# exterior_enclosure.net
KiCad netlist of a schematic drawn in EAGLE
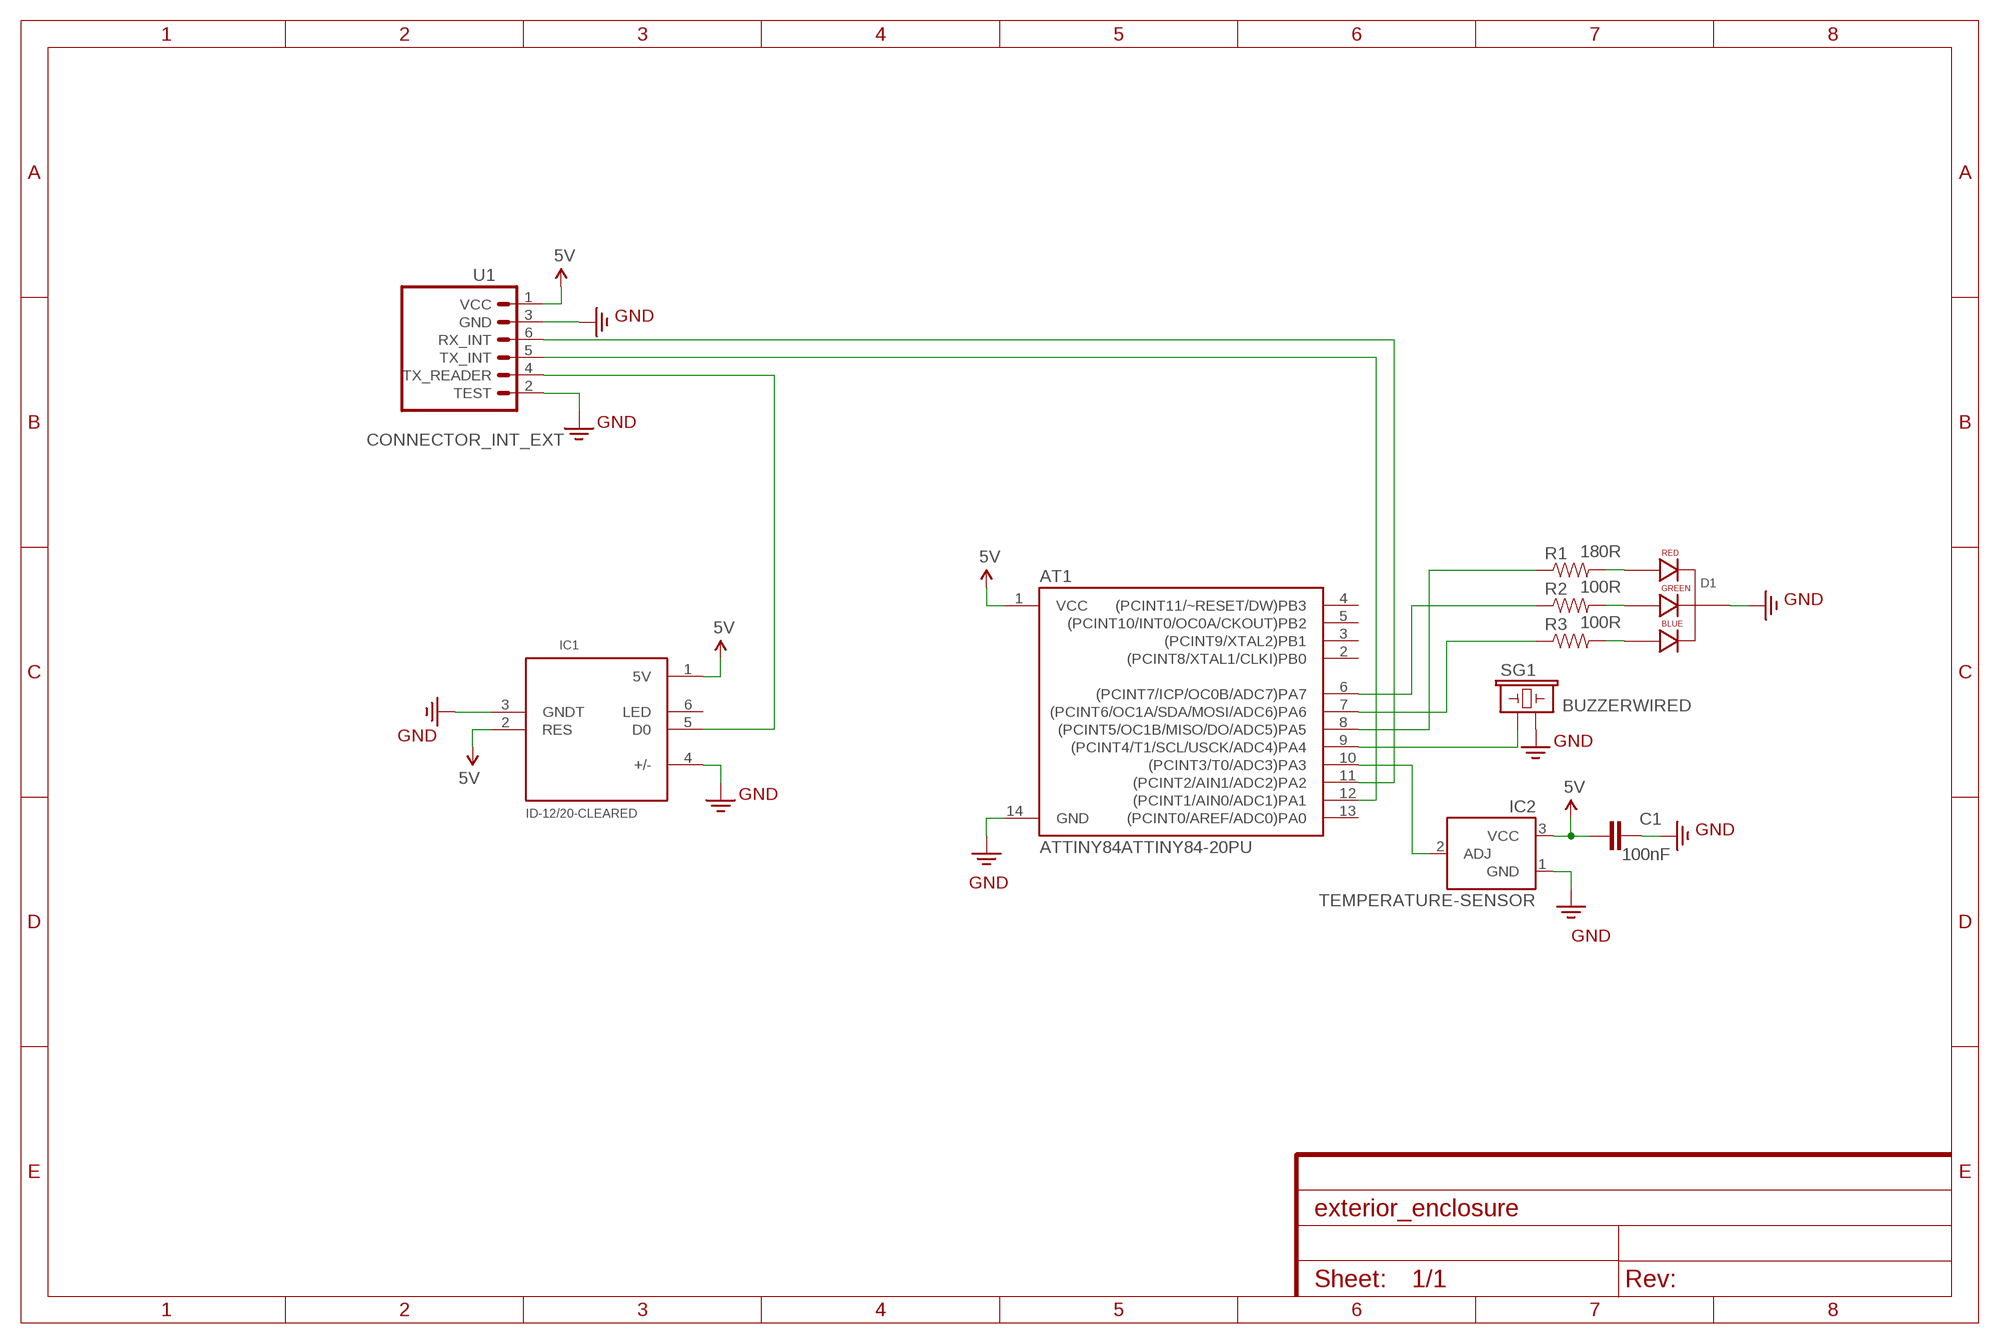
[diagram p0: schematic, sheet 1]

(export (version "E")
  (design (tool "Eeschema 10.0.6"))
  (components
    (comp (ref "AT1")
      (value "ATTINY84ATTINY84-20PU")
      (footprint "eagle-import:DIL14")
      (libsource (lib "eagle-import") (part "ATTINY84ATTINY84-20PU"))
    )
    (comp (ref "C1")
      (value "100nF")
      (footprint "eagle-import:CAP-PTH-SMALL-KIT")
      (libsource (lib "eagle-import") (part "0.1UF-50V-20%(PTH)KIT-EZ"))
    )
    (comp (ref "D1")
      (value "LED-RGB-CC-THRUCLEAR")
      (footprint "eagle-import:LED-RGB-THRU")
      (libsource (lib "eagle-import") (part "LED-RGB-CC-THRUCLEAR"))
    )
    (comp (ref "IC1")
      (value "ID-12/20-CLEARED")
      (footprint "eagle-import:1X06_COMMON")
      (libsource (lib "eagle-import") (part "ID-12/20-CLEARED"))
    )
    (comp (ref "IC2")
      (value "TEMPERATURE-SENSOR")
      (footprint "eagle-import:TO-92")
      (libsource (lib "eagle-import") (part "TEMPERATURE-SENSOR"))
    )
    (comp (ref "R1")
      (value "180R")
      (footprint "eagle-import:AXIAL-0.1")
      (libsource (lib "eagle-import") (part "RESISTORVERT"))
    )
    (comp (ref "R2")
      (value "100R")
      (footprint "eagle-import:AXIAL-0.1")
      (libsource (lib "eagle-import") (part "RESISTORVERT"))
    )
    (comp (ref "R3")
      (value "100R")
      (footprint "eagle-import:AXIAL-0.1")
      (libsource (lib "eagle-import") (part "RESISTORVERT"))
    )
    (comp (ref "SG1")
      (value "BUZZERWIRED")
      (footprint "eagle-import:1X02")
      (libsource (lib "eagle-import") (part "BUZZERWIRED"))
    )
    (comp (ref "U1")
      (value "CONNECTOR_INT_EXT")
      (footprint "eagle-import:1X06_COMMON")
      (libsource (lib "eagle-import") (part "CONNECTOR_INT_EXT"))
    )
  )
  (nets
    (net (code "1") (name "5V") (class "Default")
      (node (ref "AT1") (pin "1") (pinfunction "VCC_1") (pintype "bidirectional"))
      (node (ref "C1") (pin "1") (pinfunction "1_1") (pintype "passive"))
      (node (ref "IC1") (pin "1") (pinfunction "5V_1") (pintype "bidirectional"))
      (node (ref "IC1") (pin "2") (pinfunction "RES_2") (pintype "bidirectional"))
      (node (ref "IC2") (pin "3") (pinfunction "VCC_3") (pintype "bidirectional"))
      (node (ref "U1") (pin "1") (pinfunction "VCC_1") (pintype "passive"))
    )
    (net (code "2") (name "GND") (class "Default")
      (node (ref "AT1") (pin "14") (pinfunction "GND_14") (pintype "bidirectional"))
      (node (ref "C1") (pin "2") (pinfunction "2_2") (pintype "passive"))
      (node (ref "D1") (pin "2") (pinfunction "CATHODE_2") (pintype "bidirectional"))
      (node (ref "IC1") (pin "3") (pinfunction "GNDT_3") (pintype "bidirectional"))
      (node (ref "IC1") (pin "4") (pinfunction "+/-_4") (pintype "bidirectional"))
      (node (ref "IC2") (pin "1") (pinfunction "GND_1") (pintype "bidirectional"))
      (node (ref "SG1") (pin "2") (pinfunction "2_2") (pintype "passive"))
      (node (ref "U1") (pin "2") (pinfunction "TEST_2") (pintype "passive"))
      (node (ref "U1") (pin "3") (pinfunction "GND_3") (pintype "passive"))
    )
    (net (code "3") (name "Net-(AT1-(PCINT1{slash}AIN0{slash}ADC1)PA1)") (class "Default")
      (node (ref "AT1") (pin "12") (pinfunction "(PCINT1/AIN0/ADC1)PA1_12") (pintype "bidirectional"))
      (node (ref "U1") (pin "5") (pinfunction "TX_INT_5") (pintype "passive"))
    )
    (net (code "4") (name "Net-(AT1-(PCINT2{slash}AIN1{slash}ADC2)PA2)") (class "Default")
      (node (ref "AT1") (pin "11") (pinfunction "(PCINT2/AIN1/ADC2)PA2_11") (pintype "bidirectional"))
      (node (ref "U1") (pin "6") (pinfunction "RX_INT_6") (pintype "passive"))
    )
    (net (code "5") (name "Net-(AT1-(PCINT3{slash}T0{slash}ADC3)PA3)") (class "Default")
      (node (ref "AT1") (pin "10") (pinfunction "(PCINT3/T0/ADC3)PA3_10") (pintype "bidirectional"))
      (node (ref "IC2") (pin "2") (pinfunction "ADJ_2") (pintype "bidirectional"))
    )
    (net (code "6") (name "Net-(AT1-(PCINT4{slash}T1{slash}SCL{slash}USCK{slash}ADC4)PA4)") (class "Default")
      (node (ref "AT1") (pin "9") (pinfunction "(PCINT4/T1/SCL/USCK/ADC4)PA4_9") (pintype "bidirectional"))
      (node (ref "SG1") (pin "1") (pinfunction "1_1") (pintype "passive"))
    )
    (net (code "7") (name "Net-(AT1-(PCINT5{slash}OC1B{slash}MISO{slash}DO{slash}ADC5)PA5)") (class "Default")
      (node (ref "AT1") (pin "8") (pinfunction "(PCINT5/OC1B/MISO/DO/ADC5)PA5_8") (pintype "bidirectional"))
      (node (ref "R1") (pin "P$1") (pinfunction "1_P$1") (pintype "passive"))
    )
    (net (code "8") (name "Net-(AT1-(PCINT6{slash}OC1A{slash}SDA{slash}MOSI{slash}ADC6)PA6)") (class "Default")
      (node (ref "AT1") (pin "7") (pinfunction "(PCINT6/OC1A/SDA/MOSI/ADC6)PA6_7") (pintype "bidirectional"))
      (node (ref "R3") (pin "P$1") (pinfunction "1_P$1") (pintype "passive"))
    )
    (net (code "9") (name "Net-(AT1-(PCINT7{slash}ICP{slash}OC0B{slash}ADC7)PA7)") (class "Default")
      (node (ref "AT1") (pin "6") (pinfunction "(PCINT7/ICP/OC0B/ADC7)PA7_6") (pintype "bidirectional"))
      (node (ref "R2") (pin "P$1") (pinfunction "1_P$1") (pintype "passive"))
    )
    (net (code "10") (name "Net-(D1-BLUE_CATHODE)") (class "Default")
      (node (ref "D1") (pin "4") (pinfunction "BLUE_CATHODE_4") (pintype "bidirectional"))
      (node (ref "R3") (pin "P$2") (pinfunction "2_P$2") (pintype "passive"))
    )
    (net (code "11") (name "Net-(D1-GREEN_CATHODE)") (class "Default")
      (node (ref "D1") (pin "3") (pinfunction "GREEN_CATHODE_3") (pintype "bidirectional"))
      (node (ref "R2") (pin "P$2") (pinfunction "2_P$2") (pintype "passive"))
    )
    (net (code "12") (name "Net-(D1-RED_CATHODE)") (class "Default")
      (node (ref "D1") (pin "1") (pinfunction "RED_CATHODE_1") (pintype "bidirectional"))
      (node (ref "R1") (pin "P$2") (pinfunction "2_P$2") (pintype "passive"))
    )
    (net (code "13") (name "Net-(IC1-D0)") (class "Default")
      (node (ref "IC1") (pin "5") (pinfunction "D0_5") (pintype "bidirectional"))
      (node (ref "U1") (pin "4") (pinfunction "TX_READER_4") (pintype "passive"))
    )
    (net (code "14") (name "unconnected-(AT1-(PCINT0{slash}AREF{slash}ADC0)PA0-Pad13)") (class "Default")
      (node (ref "AT1") (pin "13") (pinfunction "(PCINT0/AREF/ADC0)PA0_13") (pintype "bidirectional"))
    )
    (net (code "15") (name "unconnected-(AT1-(PCINT8{slash}XTAL1{slash}CLKI)PB0-Pad2)") (class "Default")
      (node (ref "AT1") (pin "2") (pinfunction "(PCINT8/XTAL1/CLKI)PB0_2") (pintype "bidirectional"))
    )
    (net (code "16") (name "unconnected-(AT1-(PCINT9{slash}XTAL2)PB1-Pad3)") (class "Default")
      (node (ref "AT1") (pin "3") (pinfunction "(PCINT9/XTAL2)PB1_3") (pintype "bidirectional"))
    )
    (net (code "17") (name "unconnected-(AT1-(PCINT10{slash}INT0{slash}OC0A{slash}CKOUT)PB2-Pad5)") (class "Default")
      (node (ref "AT1") (pin "5") (pinfunction "(PCINT10/INT0/OC0A/CKOUT)PB2_5") (pintype "bidirectional"))
    )
    (net (code "18") (name "unconnected-(AT1-(PCINT11{slash}~{RESET{slash}DW})PB3-Pad4)") (class "Default")
      (node (ref "AT1") (pin "4") (pinfunction "(PCINT11/~{RESET/DW})PB3_4") (pintype "bidirectional"))
    )
    (net (code "19") (name "unconnected-(IC1-LED-Pad6)") (class "Default")
      (node (ref "IC1") (pin "6") (pinfunction "LED_6") (pintype "bidirectional"))
    )
  )
)
